# MB1-USB-r1_0.net
KiCad netlist of a schematic drawn in Altium Designer
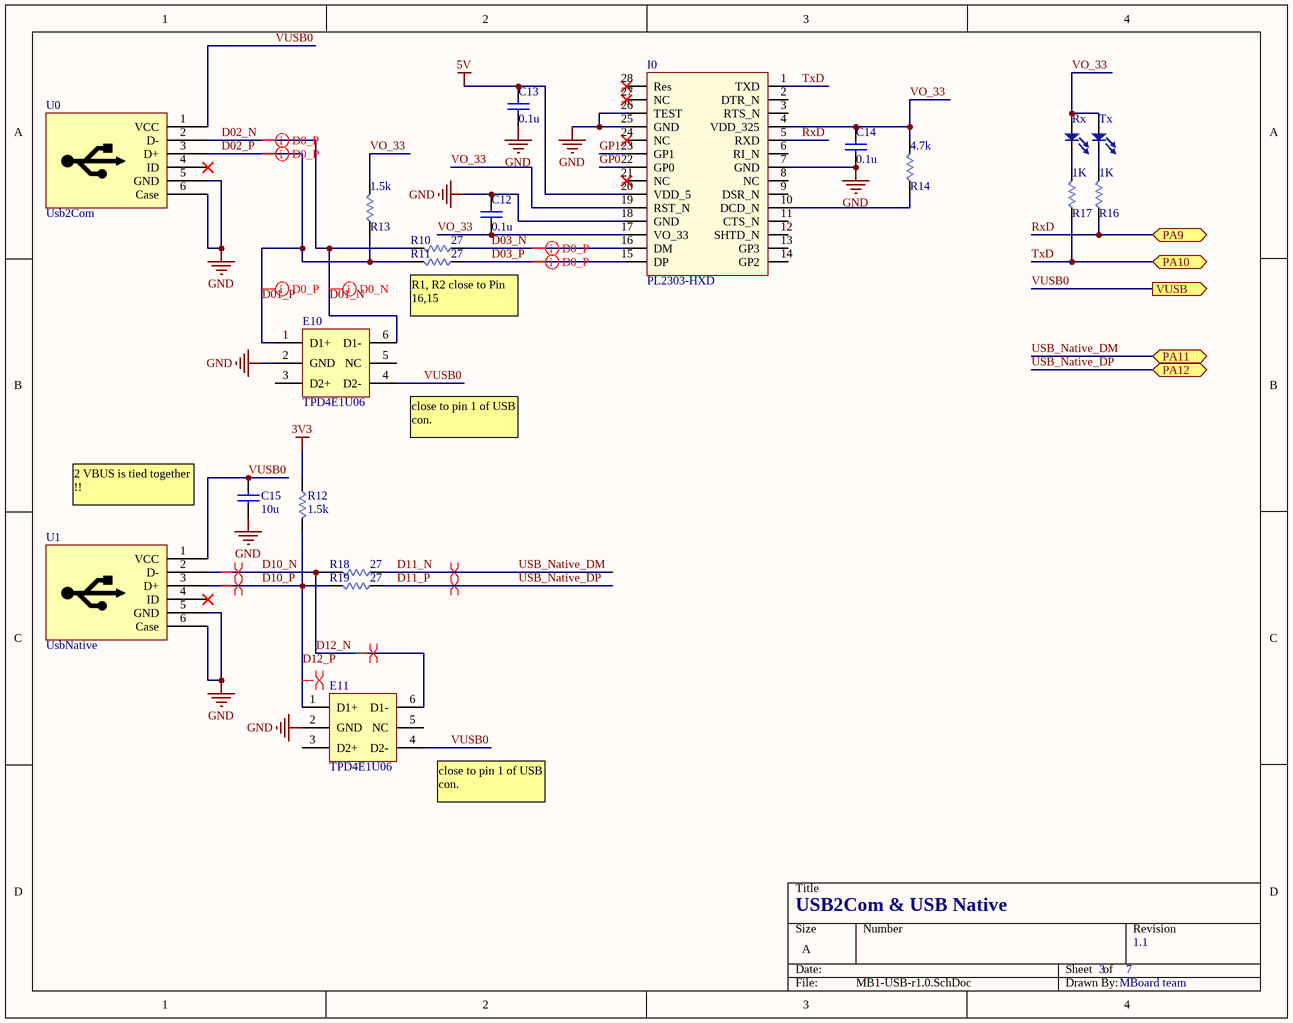
[diagram p0: MB1-USB-r1.0.SchDoc]

(export (version "E")
  (design (tool "Eeschema 10.0.6"))
  (components
    (comp (ref "C12")
      (value "0.1u")
      (footprint "SM_0805_LD")
      (description "Non-polarity ceramic capacitor")
      (fields (field (name "Comment") "CAP Ceramic") (field (name "PUBLISHER") "Altium Limited"))
      (libsource (lib "HLib_schematic_lib") (part "CAP Ceramic"))
    )
    (comp (ref "C13")
      (value "0.1u")
      (footprint "SM_0805_LD")
      (description "Non-polarity ceramic capacitor")
      (fields (field (name "Comment") "CAP Ceramic") (field (name "PUBLISHER") "Altium Limited"))
      (libsource (lib "HLib_schematic_lib") (part "CAP Ceramic"))
    )
    (comp (ref "C14")
      (value "0.1u")
      (footprint "SM_0805_LD")
      (description "Non-polarity ceramic capacitor")
      (fields (field (name "Comment") "CAP Ceramic") (field (name "PUBLISHER") "Altium Limited"))
      (libsource (lib "HLib_schematic_lib") (part "CAP Ceramic"))
    )
    (comp (ref "C15")
      (value "10u")
      (footprint "SM_0805_LD")
      (description "Non-polarity ceramic capacitor")
      (fields (field (name "Comment") "CAP Ceramic") (field (name "PUBLISHER") "Altium Limited"))
      (libsource (lib "HLib_schematic_lib") (part "CAP Ceramic"))
    )
    (comp (ref "E10") (value "TPD4E1U06") (footprint "SC70-6") (libsource (lib "MyLib") (part "TPD4E1U06")))
    (comp (ref "E11") (value "TPD4E1U06") (footprint "SC70-6") (libsource (lib "MyLib") (part "TPD4E1U06")))
    (comp (ref "I0") (value "PL2303-HXD") (footprint "SSOP-28") (libsource (lib "MyLib") (part "PL2303-HXD")))
    (comp (ref "R10")
      (value "27")
      (footprint "SM_0805_LD")
      (description "Resistor")
      (fields (field (name "PUBLISHER") "Altium Limited"))
      (libsource (lib "HLib_schematic_lib") (part "R"))
    )
    (comp (ref "R11")
      (value "27")
      (footprint "SM_0805_LD")
      (description "Resistor")
      (fields (field (name "PUBLISHER") "Altium Limited"))
      (libsource (lib "HLib_schematic_lib") (part "R"))
    )
    (comp (ref "R12")
      (value "1.5k")
      (footprint "SM_0805_LD")
      (description "Resistor")
      (fields (field (name "PUBLISHER") "Altium Limited"))
      (libsource (lib "HLib_schematic_lib") (part "R"))
    )
    (comp (ref "R13")
      (value "1.5k")
      (footprint "SM_0805_LD")
      (description "Resistor")
      (fields (field (name "PUBLISHER") "Altium Limited"))
      (libsource (lib "HLib_schematic_lib") (part "R"))
    )
    (comp (ref "R14")
      (value "4.7k")
      (footprint "SM_0805_LD")
      (description "Resistor")
      (fields (field (name "PUBLISHER") "Altium Limited"))
      (libsource (lib "HLib_schematic_lib") (part "R"))
    )
    (comp (ref "R16")
      (value "1K")
      (footprint "SM_0805_LD")
      (description "Resistor")
      (fields (field (name "PUBLISHER") "Altium Limited"))
      (libsource (lib "HLib_schematic_lib") (part "R"))
    )
    (comp (ref "R17")
      (value "1K")
      (footprint "SM_0805_LD")
      (description "Resistor")
      (fields (field (name "PUBLISHER") "Altium Limited"))
      (libsource (lib "HLib_schematic_lib") (part "R"))
    )
    (comp (ref "R18")
      (value "27")
      (footprint "SM_0805_LD")
      (description "Resistor")
      (fields (field (name "PUBLISHER") "Altium Limited"))
      (libsource (lib "HLib_schematic_lib") (part "R"))
    )
    (comp (ref "R19")
      (value "27")
      (footprint "SM_0805_LD")
      (description "Resistor")
      (fields (field (name "PUBLISHER") "Altium Limited"))
      (libsource (lib "HLib_schematic_lib") (part "R"))
    )
    (comp (ref "Rx")
      (value "Blue")
      (footprint "SM_0805_POL_LD")
      (description "LED")
      (fields (field (name "PUBLISHER") "Altium Limited"))
      (libsource (lib "HLib_schematic_lib") (part "LED"))
    )
    (comp (ref "Tx")
      (value "Green")
      (footprint "SM_0805_POL_LD")
      (description "LED")
      (fields (field (name "PUBLISHER") "Altium Limited"))
      (libsource (lib "HLib_schematic_lib") (part "LED"))
    )
    (comp (ref "U0") (value "Usb2Com") (footprint "USB-mini-B") (libsource (lib "MyLib") (part "USB-Mini-B")))
    (comp (ref "U1")
      (value "UsbNative")
      (footprint "USB-mini-B")
      (libsource (lib "MyLib") (part "USB-Mini-B"))
    )
  )
  (nets
    (net (code "1") (name "/D01_N") (class "Default")
      (node (ref "E10") (pin "6") (pinfunction "D1-_6") (pintype "passive"))
      (node (ref "R10") (pin "2") (pinfunction "2_2") (pintype "passive"))
      (node (ref "U0") (pin "2") (pinfunction "D-_2") (pintype "passive"))
    )
    (net (code "2") (name "/D01_P") (class "Default")
      (node (ref "E10") (pin "1") (pinfunction "D1+_1") (pintype "passive"))
      (node (ref "R11") (pin "2") (pinfunction "2_2") (pintype "passive"))
      (node (ref "R13") (pin "1") (pinfunction "1_1") (pintype "passive"))
      (node (ref "U0") (pin "3") (pinfunction "D+_3") (pintype "passive"))
    )
    (net (code "3") (name "/D03_N") (class "Default")
      (node (ref "I0") (pin "16") (pinfunction "DM_16") (pintype "passive"))
      (node (ref "R10") (pin "1") (pinfunction "1_1") (pintype "passive"))
    )
    (net (code "4") (name "/D03_P") (class "Default")
      (node (ref "I0") (pin "15") (pinfunction "DP_15") (pintype "passive"))
      (node (ref "R11") (pin "1") (pinfunction "1_1") (pintype "passive"))
    )
    (net (code "5") (name "/D10_N") (class "Default")
      (node (ref "E11") (pin "6") (pinfunction "D1-_6") (pintype "passive"))
      (node (ref "R18") (pin "2") (pinfunction "2_2") (pintype "passive"))
      (node (ref "U1") (pin "2") (pinfunction "D-_2") (pintype "passive"))
    )
    (net (code "6") (name "/D10_P") (class "Default")
      (node (ref "E11") (pin "1") (pinfunction "D1+_1") (pintype "passive"))
      (node (ref "R12") (pin "2") (pinfunction "2_2") (pintype "passive"))
      (node (ref "R19") (pin "2") (pinfunction "2_2") (pintype "passive"))
      (node (ref "U1") (pin "3") (pinfunction "D+_3") (pintype "passive"))
    )
    (net (code "7") (name "/D11_N") (class "Default")
      (node (ref "R18") (pin "1") (pinfunction "1_1") (pintype "passive"))
    )
    (net (code "8") (name "/D11_P") (class "Default")
      (node (ref "R19") (pin "1") (pinfunction "1_1") (pintype "passive"))
    )
    (net (code "9") (name "/GP0") (class "Default")
      (node (ref "I0") (pin "22") (pinfunction "GP0_22") (pintype "passive"))
    )
    (net (code "10") (name "/GP1") (class "Default")
      (node (ref "I0") (pin "23") (pinfunction "GP1_23") (pintype "passive"))
    )
    (net (code "11") (name "/RxD") (class "Default")
      (node (ref "I0") (pin "5") (pinfunction "RXD_5") (pintype "passive"))
      (node (ref "R16") (pin "1") (pinfunction "1_1") (pintype "passive"))
    )
    (net (code "12") (name "/TxD") (class "Default")
      (node (ref "I0") (pin "1") (pinfunction "TXD_1") (pintype "passive"))
      (node (ref "R17") (pin "1") (pinfunction "1_1") (pintype "passive"))
    )
    (net (code "13") (name "/VO_33") (class "Default")
      (node (ref "C12") (pin "1") (pinfunction "1_1") (pintype "passive"))
      (node (ref "C14") (pin "2") (pinfunction "2_2") (pintype "passive"))
      (node (ref "I0") (pin "17") (pinfunction "VO_33_17") (pintype "passive"))
      (node (ref "I0") (pin "19") (pinfunction "RST_N_19") (pintype "passive"))
      (node (ref "I0") (pin "4") (pinfunction "VDD_325_4") (pintype "passive"))
      (node (ref "R13") (pin "2") (pinfunction "2_2") (pintype "passive"))
      (node (ref "R14") (pin "2") (pinfunction "2_2") (pintype "passive"))
      (node (ref "Rx") (pin "1") (pinfunction "A_1") (pintype "passive"))
      (node (ref "Tx") (pin "1") (pinfunction "A_1") (pintype "passive"))
    )
    (net (code "14") (name "/VUSB0") (class "Default")
      (node (ref "C15") (pin "2") (pinfunction "2_2") (pintype "passive"))
      (node (ref "E10") (pin "4") (pinfunction "D2-_4") (pintype "passive"))
      (node (ref "E11") (pin "4") (pinfunction "D2-_4") (pintype "passive"))
      (node (ref "U0") (pin "1") (pinfunction "VCC_1") (pintype "passive"))
      (node (ref "U1") (pin "1") (pinfunction "VCC_1") (pintype "passive"))
    )
    (net (code "15") (name "3V3") (class "Default")
      (node (ref "R12") (pin "1") (pinfunction "1_1") (pintype "passive"))
    )
    (net (code "16") (name "5V") (class "Default")
      (node (ref "C13") (pin "2") (pinfunction "2_2") (pintype "passive"))
      (node (ref "I0") (pin "20") (pinfunction "VDD_5_20") (pintype "passive"))
    )
    (net (code "17") (name "GND") (class "Default")
      (node (ref "C12") (pin "2") (pinfunction "2_2") (pintype "passive"))
      (node (ref "C13") (pin "1") (pinfunction "1_1") (pintype "passive"))
      (node (ref "C14") (pin "1") (pinfunction "1_1") (pintype "passive"))
      (node (ref "C15") (pin "1") (pinfunction "1_1") (pintype "passive"))
      (node (ref "E10") (pin "2") (pinfunction "GND_2") (pintype "passive"))
      (node (ref "E11") (pin "2") (pinfunction "GND_2") (pintype "passive"))
      (node (ref "I0") (pin "18") (pinfunction "GND_18") (pintype "passive"))
      (node (ref "I0") (pin "25") (pinfunction "GND_25") (pintype "passive"))
      (node (ref "I0") (pin "26") (pinfunction "TEST_26") (pintype "passive"))
      (node (ref "I0") (pin "7") (pinfunction "GND_7") (pintype "passive"))
      (node (ref "U0") (pin "5") (pinfunction "GND_5") (pintype "passive"))
      (node (ref "U0") (pin "6") (pinfunction "Case_6") (pintype "power_in"))
      (node (ref "U1") (pin "5") (pinfunction "GND_5") (pintype "passive"))
      (node (ref "U1") (pin "6") (pinfunction "Case_6") (pintype "power_in"))
    )
    (net (code "18") (name "Net-(I0-DCD_N)") (class "Default")
      (node (ref "I0") (pin "10") (pinfunction "DCD_N_10") (pintype "passive"))
      (node (ref "R14") (pin "1") (pinfunction "1_1") (pintype "passive"))
    )
    (net (code "19") (name "Net-(Rx-K)") (class "Default")
      (node (ref "R17") (pin "2") (pinfunction "2_2") (pintype "passive"))
      (node (ref "Rx") (pin "2") (pinfunction "K_2") (pintype "passive"))
    )
    (net (code "20") (name "Net-(Tx-K)") (class "Default")
      (node (ref "R16") (pin "2") (pinfunction "2_2") (pintype "passive"))
      (node (ref "Tx") (pin "2") (pinfunction "K_2") (pintype "passive"))
    )
    (net (code "21") (name "unconnected-(E10-D2+-Pad3)") (class "Default")
      (node (ref "E10") (pin "3") (pinfunction "D2+_3") (pintype "passive"))
    )
    (net (code "22") (name "unconnected-(E10-NC-Pad5)") (class "Default")
      (node (ref "E10") (pin "5") (pinfunction "NC_5") (pintype "passive"))
    )
    (net (code "23") (name "unconnected-(E11-D2+-Pad3)") (class "Default")
      (node (ref "E11") (pin "3") (pinfunction "D2+_3") (pintype "passive"))
    )
    (net (code "24") (name "unconnected-(E11-NC-Pad5)") (class "Default")
      (node (ref "E11") (pin "5") (pinfunction "NC_5") (pintype "passive"))
    )
    (net (code "25") (name "unconnected-(I0-CTS_N-Pad11)") (class "Default")
      (node (ref "I0") (pin "11") (pinfunction "CTS_N_11") (pintype "passive"))
    )
    (net (code "26") (name "unconnected-(I0-DSR_N-Pad9)") (class "Default")
      (node (ref "I0") (pin "9") (pinfunction "DSR_N_9") (pintype "passive"))
    )
    (net (code "27") (name "unconnected-(I0-DTR_N-Pad2)") (class "Default")
      (node (ref "I0") (pin "2") (pinfunction "DTR_N_2") (pintype "passive"))
    )
    (net (code "28") (name "unconnected-(I0-GP2-Pad14)") (class "Default")
      (node (ref "I0") (pin "14") (pinfunction "GP2_14") (pintype "passive"))
    )
    (net (code "29") (name "unconnected-(I0-GP3-Pad13)") (class "Default")
      (node (ref "I0") (pin "13") (pinfunction "GP3_13") (pintype "passive"))
    )
    (net (code "30") (name "unconnected-(I0-NC-Pad8)") (class "Default")
      (node (ref "I0") (pin "8") (pinfunction "NC_8") (pintype "passive"))
    )
    (net (code "31") (name "unconnected-(I0-NC-Pad21)") (class "Default")
      (node (ref "I0") (pin "21") (pinfunction "NC_21") (pintype "passive+no_connect"))
    )
    (net (code "32") (name "unconnected-(I0-NC-Pad24)") (class "Default")
      (node (ref "I0") (pin "24") (pinfunction "NC_24") (pintype "passive+no_connect"))
    )
    (net (code "33") (name "unconnected-(I0-NC-Pad27)") (class "Default")
      (node (ref "I0") (pin "27") (pinfunction "NC_27") (pintype "passive+no_connect"))
    )
    (net (code "34") (name "unconnected-(I0-RI_N-Pad6)") (class "Default")
      (node (ref "I0") (pin "6") (pinfunction "RI_N_6") (pintype "passive"))
    )
    (net (code "35") (name "unconnected-(I0-RTS_N-Pad3)") (class "Default")
      (node (ref "I0") (pin "3") (pinfunction "RTS_N_3") (pintype "passive"))
    )
    (net (code "36") (name "unconnected-(I0-Res-Pad28)") (class "Default")
      (node (ref "I0") (pin "28") (pinfunction "Res_28") (pintype "passive+no_connect"))
    )
    (net (code "37") (name "unconnected-(I0-SHTD_N-Pad12)") (class "Default")
      (node (ref "I0") (pin "12") (pinfunction "SHTD_N_12") (pintype "passive"))
    )
    (net (code "38") (name "unconnected-(U0-ID-Pad4)") (class "Default")
      (node (ref "U0") (pin "4") (pinfunction "ID_4") (pintype "passive+no_connect"))
    )
    (net (code "39") (name "unconnected-(U1-ID-Pad4)") (class "Default")
      (node (ref "U1") (pin "4") (pinfunction "ID_4") (pintype "passive+no_connect"))
    )
  )
)
